# EM7180_LSM6DSM_LIS2MDL_LPS22HD_v01a.net
KiCad netlist of a schematic drawn in EAGLE
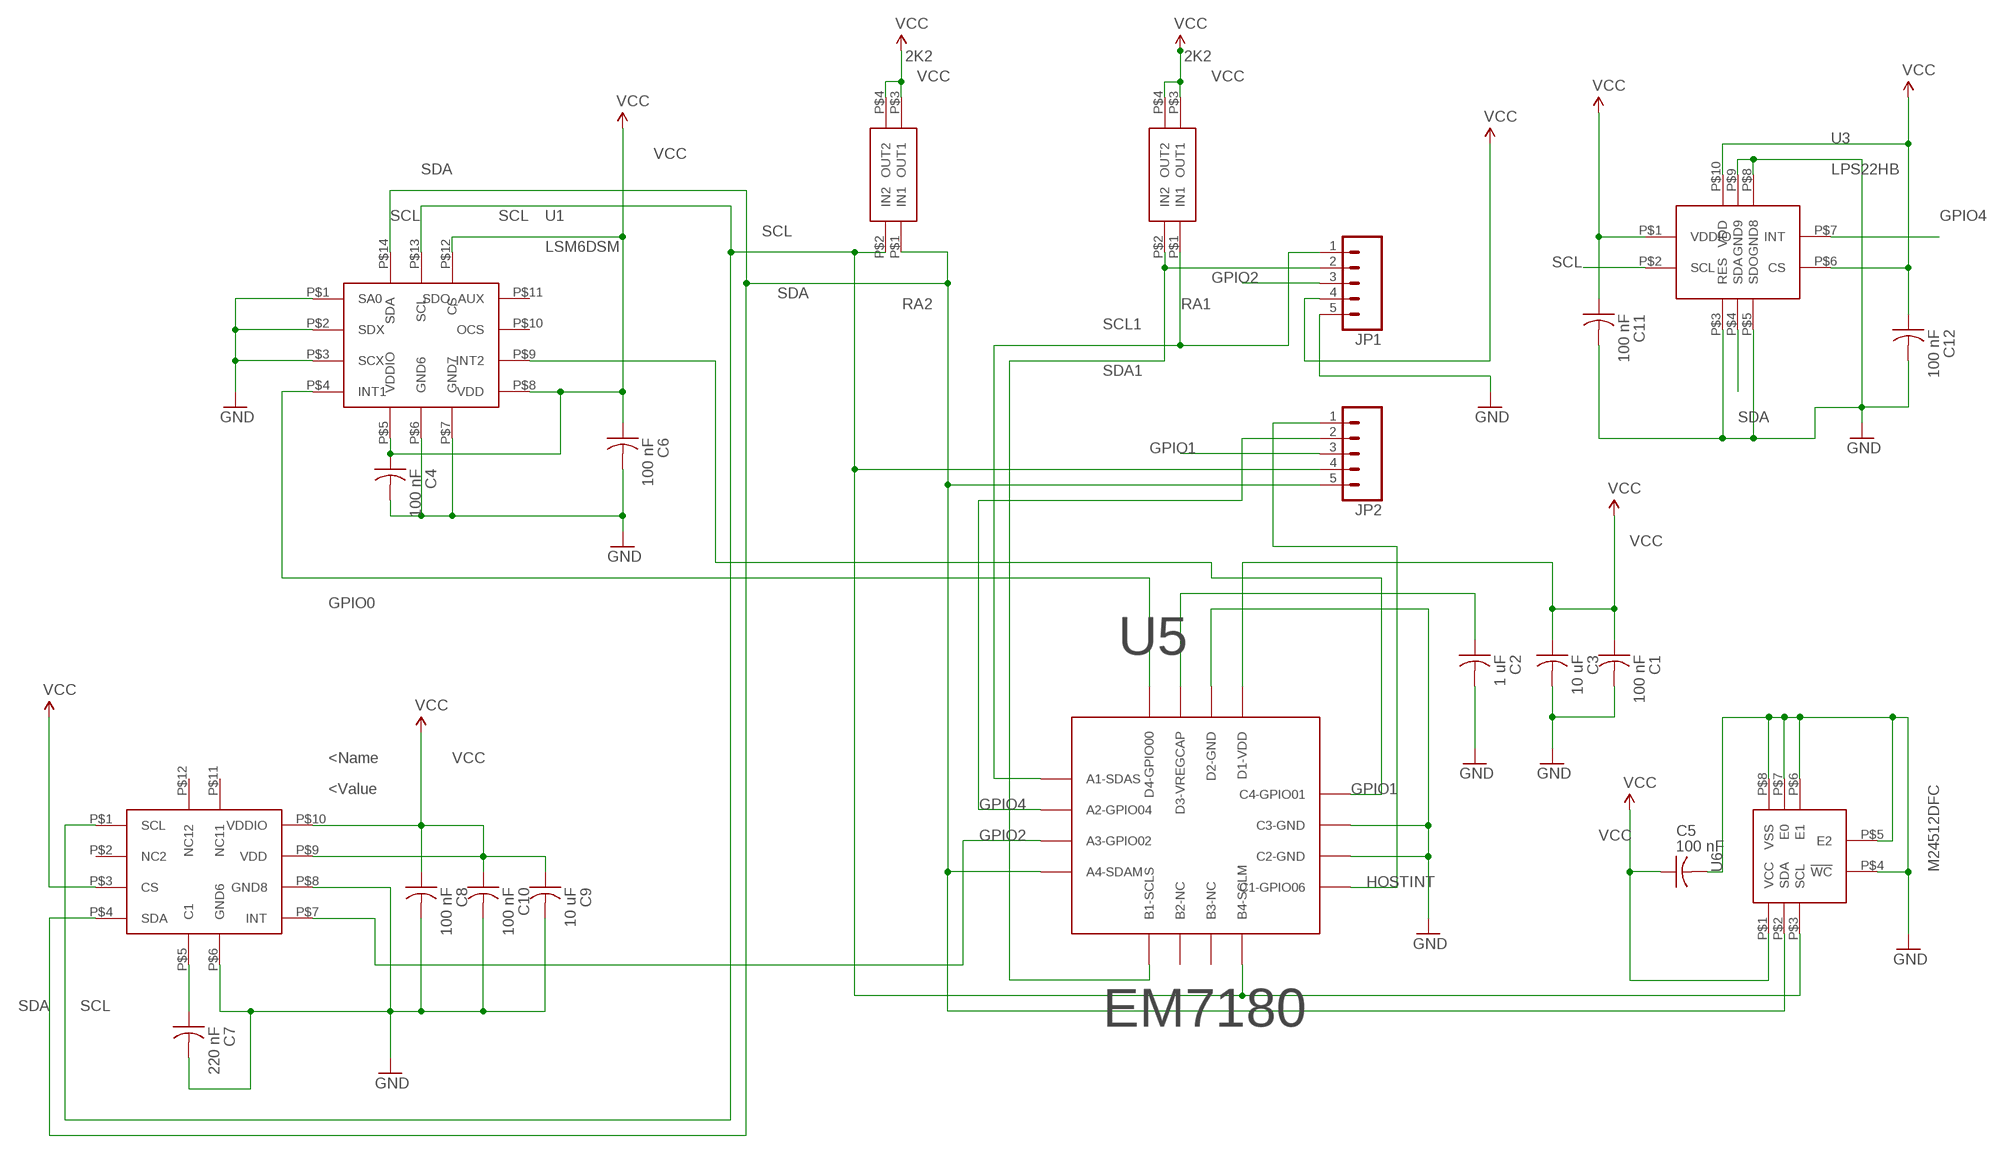
[diagram p0: schematic, sheet 1]

(export (version "E")
  (design (tool "Eeschema 10.0.6"))
  (components
    (comp (ref "C1")
      (value "100 nF")
      (footprint "eagle-import:C0402_B")
      (libsource (lib "eagle-import") (part "C-US"))
    )
    (comp (ref "C2")
      (value "1 uF")
      (footprint "eagle-import:C0402_B")
      (libsource (lib "eagle-import") (part "C-US"))
    )
    (comp (ref "C3")
      (value "10 uF")
      (footprint "eagle-import:C0402_B")
      (libsource (lib "eagle-import") (part "C-US"))
    )
    (comp (ref "C4")
      (value "100 nF")
      (footprint "eagle-import:C0402_B")
      (libsource (lib "eagle-import") (part "C-US"))
    )
    (comp (ref "C5")
      (value "100 nF")
      (footprint "eagle-import:C0402_B")
      (libsource (lib "eagle-import") (part "C-US"))
    )
    (comp (ref "C6")
      (value "100 nF")
      (footprint "eagle-import:C0402_B")
      (libsource (lib "eagle-import") (part "C-US"))
    )
    (comp (ref "C7")
      (value "220 nF")
      (footprint "eagle-import:C0402_B")
      (libsource (lib "eagle-import") (part "C-US"))
    )
    (comp (ref "C8")
      (value "100 nF")
      (footprint "eagle-import:C0402_B")
      (libsource (lib "eagle-import") (part "C-US"))
    )
    (comp (ref "C9")
      (value "10 uF")
      (footprint "eagle-import:C0402_B")
      (libsource (lib "eagle-import") (part "C-US"))
    )
    (comp (ref "C10")
      (value "100 nF")
      (footprint "eagle-import:C0402_B")
      (libsource (lib "eagle-import") (part "C-US"))
    )
    (comp (ref "C11")
      (value "100 nF")
      (footprint "eagle-import:C0402_B")
      (libsource (lib "eagle-import") (part "C-US"))
    )
    (comp (ref "C12")
      (value "100 nF")
      (footprint "eagle-import:C0402_B")
      (libsource (lib "eagle-import") (part "C-US"))
    )
    (comp (ref "JP1")
      (value "M05NO_SILK")
      (footprint "eagle-import:1X05_NO_SILK")
      (libsource (lib "eagle-import") (part "M05NO_SILK"))
    )
    (comp (ref "JP2")
      (value "M05NO_SILK")
      (footprint "eagle-import:1X05_NO_SILK")
      (libsource (lib "eagle-import") (part "M05NO_SILK"))
    )
    (comp (ref "RA1")
      (value "2K2")
      (footprint "eagle-import:EXB24V")
      (libsource (lib "eagle-import") (part "EXB24V"))
    )
    (comp (ref "RA2")
      (value "2K2")
      (footprint "eagle-import:EXB24V")
      (libsource (lib "eagle-import") (part "EXB24V"))
    )
    (comp (ref "U1")
      (value "LSM6DSM")
      (footprint "eagle-import:LSM6DSM")
      (libsource (lib "eagle-import") (part "LSM6DSM"))
    )
    (comp (ref "U2")
      (value "LIS2MDL")
      (footprint "eagle-import:LIS2MDL")
      (libsource (lib "eagle-import") (part "LIS2MDL"))
    )
    (comp (ref "U3")
      (value "LPS22HB")
      (footprint "eagle-import:LPS22HB")
      (libsource (lib "eagle-import") (part "LPS22HB"))
    )
    (comp (ref "U5")
      (value "EM7180")
      (footprint "eagle-import:WL-CSP16")
      (libsource (lib "eagle-import") (part "EM7180"))
    )
    (comp (ref "U6")
      (value "M24512DFC")
      (footprint "eagle-import:M24512DFC")
      (libsource (lib "eagle-import") (part "M24512DFC"))
    )
  )
  (nets
    (net (code "1") (name "/GPIO0") (class "Default")
      (node (ref "U1") (pin "P$4") (pinfunction "INT1_P$4") (pintype "bidirectional"))
      (node (ref "U5") (pin "P$16") (pinfunction "D4-GPIO00_P$16") (pintype "bidirectional"))
    )
    (net (code "2") (name "/GPIO1") (class "Default")
      (node (ref "JP2") (pin "3") (pinfunction "3_3") (pintype "passive"))
      (node (ref "U1") (pin "P$9") (pinfunction "INT2_P$9") (pintype "bidirectional"))
      (node (ref "U5") (pin "P$12") (pinfunction "C4-GPIO01_P$12") (pintype "bidirectional"))
    )
    (net (code "3") (name "/GPIO2") (class "Default")
      (node (ref "JP1") (pin "3") (pinfunction "3_3") (pintype "passive"))
      (node (ref "U2") (pin "P$7") (pinfunction "INT_P$7") (pintype "bidirectional"))
      (node (ref "U5") (pin "P$3") (pinfunction "A3-GPIO02_P$3") (pintype "bidirectional"))
    )
    (net (code "4") (name "/GPIO4") (class "Default")
      (node (ref "JP2") (pin "2") (pinfunction "2_2") (pintype "passive"))
      (node (ref "U3") (pin "P$7") (pinfunction "INT_P$7") (pintype "bidirectional"))
      (node (ref "U5") (pin "P$2") (pinfunction "A2-GPIO04_P$2") (pintype "bidirectional"))
    )
    (net (code "5") (name "/HOSTINT") (class "Default")
      (node (ref "JP2") (pin "1") (pinfunction "1_1") (pintype "passive"))
      (node (ref "U5") (pin "P$9") (pinfunction "C1-GPIO06_P$9") (pintype "bidirectional"))
    )
    (net (code "6") (name "/OCS") (class "Default")
      (node (ref "U1") (pin "P$10") (pinfunction "OCS_P$10") (pintype "power_in"))
    )
    (net (code "7") (name "/SCL") (class "Default")
      (node (ref "JP2") (pin "4") (pinfunction "4_4") (pintype "passive"))
      (node (ref "RA2") (pin "P$2") (pinfunction "IN2_P$2") (pintype "bidirectional"))
      (node (ref "U1") (pin "P$13") (pinfunction "SCL_P$13") (pintype "bidirectional"))
      (node (ref "U2") (pin "P$1") (pinfunction "SCL_P$1") (pintype "bidirectional"))
      (node (ref "U3") (pin "P$2") (pinfunction "SCL_P$2") (pintype "bidirectional"))
      (node (ref "U5") (pin "P$8") (pinfunction "B4-SCLM_P$8") (pintype "bidirectional"))
      (node (ref "U6") (pin "P$3") (pinfunction "SCL_P$3") (pintype "input"))
    )
    (net (code "8") (name "/SCL1") (class "Default")
      (node (ref "JP1") (pin "1") (pinfunction "1_1") (pintype "passive"))
      (node (ref "RA1") (pin "P$1") (pinfunction "IN1_P$1") (pintype "bidirectional"))
      (node (ref "U5") (pin "P$1") (pinfunction "A1-SDAS_P$1") (pintype "bidirectional"))
    )
    (net (code "9") (name "/SDA") (class "Default")
      (node (ref "JP2") (pin "5") (pinfunction "5_5") (pintype "passive"))
      (node (ref "RA2") (pin "P$1") (pinfunction "IN1_P$1") (pintype "bidirectional"))
      (node (ref "U1") (pin "P$14") (pinfunction "SDA_P$14") (pintype "bidirectional"))
      (node (ref "U2") (pin "P$4") (pinfunction "SDA_P$4") (pintype "bidirectional"))
      (node (ref "U3") (pin "P$4") (pinfunction "SDA_P$4") (pintype "bidirectional"))
      (node (ref "U5") (pin "P$4") (pinfunction "A4-SDAM_P$4") (pintype "bidirectional"))
      (node (ref "U6") (pin "P$2") (pinfunction "SDA_P$2") (pintype "bidirectional"))
    )
    (net (code "10") (name "/SDA1") (class "Default")
      (node (ref "JP1") (pin "2") (pinfunction "2_2") (pintype "passive"))
      (node (ref "RA1") (pin "P$2") (pinfunction "IN2_P$2") (pintype "bidirectional"))
      (node (ref "U5") (pin "P$5") (pinfunction "B1-SCLS_P$5") (pintype "bidirectional"))
    )
    (net (code "11") (name "/SDO_AUX") (class "Default")
      (node (ref "U1") (pin "P$11") (pinfunction "SDO_AUX_P$11") (pintype "power_in"))
    )
    (net (code "12") (name "GND") (class "Default")
      (node (ref "C1") (pin "2") (pinfunction "2_2") (pintype "passive"))
      (node (ref "C10") (pin "2") (pinfunction "2_2") (pintype "passive"))
      (node (ref "C11") (pin "2") (pinfunction "2_2") (pintype "passive"))
      (node (ref "C12") (pin "2") (pinfunction "2_2") (pintype "passive"))
      (node (ref "C2") (pin "2") (pinfunction "2_2") (pintype "passive"))
      (node (ref "C3") (pin "2") (pinfunction "2_2") (pintype "passive"))
      (node (ref "C4") (pin "2") (pinfunction "2_2") (pintype "passive"))
      (node (ref "C5") (pin "2") (pinfunction "2_2") (pintype "passive"))
      (node (ref "C6") (pin "2") (pinfunction "2_2") (pintype "passive"))
      (node (ref "C7") (pin "2") (pinfunction "2_2") (pintype "passive"))
      (node (ref "C8") (pin "2") (pinfunction "2_2") (pintype "passive"))
      (node (ref "C9") (pin "2") (pinfunction "2_2") (pintype "passive"))
      (node (ref "JP1") (pin "5") (pinfunction "5_5") (pintype "passive"))
      (node (ref "U1") (pin "P$1") (pinfunction "SA0_P$1") (pintype "bidirectional"))
      (node (ref "U1") (pin "P$2") (pinfunction "SDX_P$2") (pintype "power_in"))
      (node (ref "U1") (pin "P$3") (pinfunction "SCX_P$3") (pintype "power_in"))
      (node (ref "U1") (pin "P$6") (pinfunction "GND6_P$6") (pintype "power_in"))
      (node (ref "U1") (pin "P$7") (pinfunction "GND7_P$7") (pintype "power_in"))
      (node (ref "U2") (pin "P$6") (pinfunction "GND6_P$6") (pintype "power_in"))
      (node (ref "U2") (pin "P$8") (pinfunction "GND8_P$8") (pintype "power_in"))
      (node (ref "U3") (pin "P$3") (pinfunction "RES_P$3") (pintype "bidirectional"))
      (node (ref "U3") (pin "P$5") (pinfunction "SDO_P$5") (pintype "bidirectional"))
      (node (ref "U3") (pin "P$8") (pinfunction "GND8_P$8") (pintype "power_in"))
      (node (ref "U3") (pin "P$9") (pinfunction "GND9_P$9") (pintype "power_in"))
      (node (ref "U5") (pin "P$10") (pinfunction "C2-GND_P$10") (pintype "power_in"))
      (node (ref "U5") (pin "P$11") (pinfunction "C3-GND_P$11") (pintype "power_in"))
      (node (ref "U5") (pin "P$14") (pinfunction "D2-GND_P$14") (pintype "power_in"))
      (node (ref "U6") (pin "P$4") (pinfunction "~{WC}_P$4") (pintype "input"))
      (node (ref "U6") (pin "P$5") (pinfunction "E2_P$5") (pintype "input"))
      (node (ref "U6") (pin "P$6") (pinfunction "E1_P$6") (pintype "input"))
      (node (ref "U6") (pin "P$7") (pinfunction "E0_P$7") (pintype "input"))
      (node (ref "U6") (pin "P$8") (pinfunction "VSS_P$8") (pintype "power_in"))
    )
    (net (code "13") (name "Net-(U2-C1)") (class "Default")
      (node (ref "C7") (pin "1") (pinfunction "1_1") (pintype "passive"))
      (node (ref "U2") (pin "P$5") (pinfunction "C1_P$5") (pintype "power_in"))
    )
    (net (code "14") (name "Net-(U5-D3-VREGCAP)") (class "Default")
      (node (ref "C2") (pin "1") (pinfunction "1_1") (pintype "passive"))
      (node (ref "U5") (pin "P$15") (pinfunction "D3-VREGCAP_P$15") (pintype "bidirectional"))
    )
    (net (code "15") (name "VCC") (class "Default")
      (node (ref "C1") (pin "1") (pinfunction "1_1") (pintype "passive"))
      (node (ref "C10") (pin "1") (pinfunction "1_1") (pintype "passive"))
      (node (ref "C11") (pin "1") (pinfunction "1_1") (pintype "passive"))
      (node (ref "C12") (pin "1") (pinfunction "1_1") (pintype "passive"))
      (node (ref "C3") (pin "1") (pinfunction "1_1") (pintype "passive"))
      (node (ref "C4") (pin "1") (pinfunction "1_1") (pintype "passive"))
      (node (ref "C5") (pin "1") (pinfunction "1_1") (pintype "passive"))
      (node (ref "C6") (pin "1") (pinfunction "1_1") (pintype "passive"))
      (node (ref "C8") (pin "1") (pinfunction "1_1") (pintype "passive"))
      (node (ref "C9") (pin "1") (pinfunction "1_1") (pintype "passive"))
      (node (ref "JP1") (pin "4") (pinfunction "4_4") (pintype "passive"))
      (node (ref "RA1") (pin "P$3") (pinfunction "OUT1_P$3") (pintype "bidirectional"))
      (node (ref "RA1") (pin "P$4") (pinfunction "OUT2_P$4") (pintype "bidirectional"))
      (node (ref "RA2") (pin "P$3") (pinfunction "OUT1_P$3") (pintype "bidirectional"))
      (node (ref "RA2") (pin "P$4") (pinfunction "OUT2_P$4") (pintype "bidirectional"))
      (node (ref "U1") (pin "P$12") (pinfunction "CS_P$12") (pintype "power_in"))
      (node (ref "U1") (pin "P$5") (pinfunction "VDDIO_P$5") (pintype "power_in"))
      (node (ref "U1") (pin "P$8") (pinfunction "VDD_P$8") (pintype "power_in"))
      (node (ref "U2") (pin "P$10") (pinfunction "VDDIO_P$10") (pintype "power_in"))
      (node (ref "U2") (pin "P$3") (pinfunction "CS_P$3") (pintype "bidirectional"))
      (node (ref "U2") (pin "P$9") (pinfunction "VDD_P$9") (pintype "power_in"))
      (node (ref "U3") (pin "P$1") (pinfunction "VDDIO_P$1") (pintype "power_in"))
      (node (ref "U3") (pin "P$10") (pinfunction "VDD_P$10") (pintype "power_in"))
      (node (ref "U3") (pin "P$6") (pinfunction "CS_P$6") (pintype "bidirectional"))
      (node (ref "U5") (pin "P$13") (pinfunction "D1-VDD_P$13") (pintype "power_in"))
      (node (ref "U6") (pin "P$1") (pinfunction "VCC_P$1") (pintype "power_in"))
    )
    (net (code "16") (name "unconnected-(U2-NC2-PadP$2)") (class "Default")
      (node (ref "U2") (pin "P$2") (pinfunction "NC2_P$2") (pintype "no_connect"))
    )
    (net (code "17") (name "unconnected-(U2-NC11-PadP$11)") (class "Default")
      (node (ref "U2") (pin "P$11") (pinfunction "NC11_P$11") (pintype "no_connect"))
    )
    (net (code "18") (name "unconnected-(U2-NC12-PadP$12)") (class "Default")
      (node (ref "U2") (pin "P$12") (pinfunction "NC12_P$12") (pintype "no_connect"))
    )
    (net (code "19") (name "unconnected-(U5-B2-NC-PadP$6)") (class "Default")
      (node (ref "U5") (pin "P$6") (pinfunction "B2-NC_P$6") (pintype "bidirectional"))
    )
    (net (code "20") (name "unconnected-(U5-B3-NC-PadP$7)") (class "Default")
      (node (ref "U5") (pin "P$7") (pinfunction "B3-NC_P$7") (pintype "bidirectional"))
    )
  )
)
